# OKADIRI_1stGroup.net
KiCad netlist of a schematic drawn in EAGLE
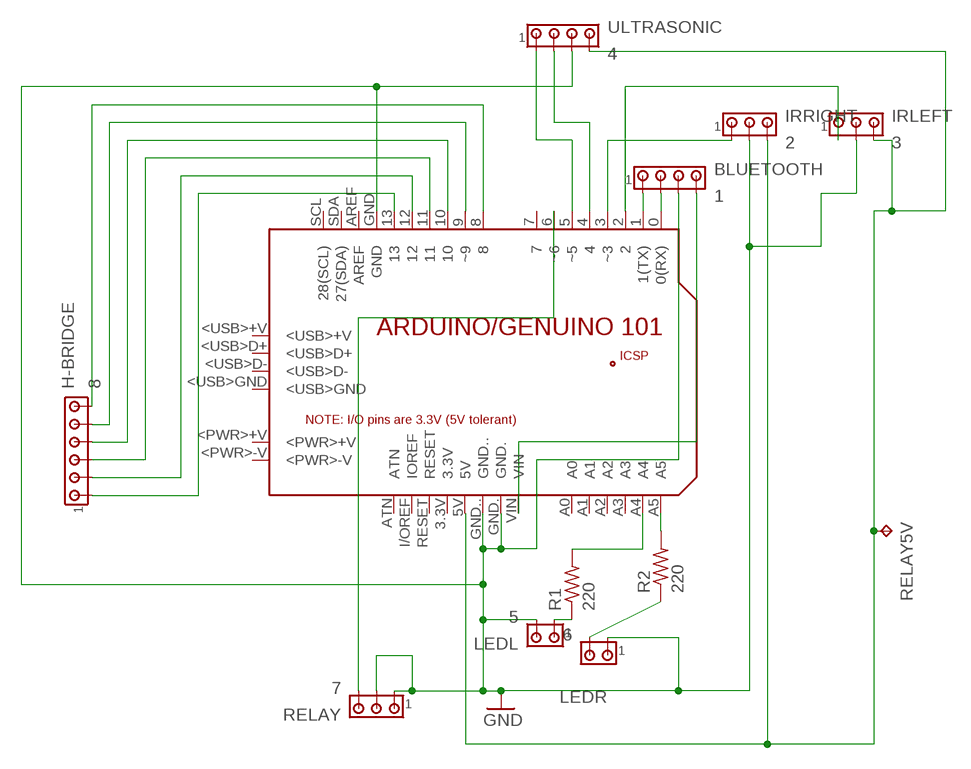
[diagram p0: schematic, sheet 1]

(export (version "E")
  (design (tool "Eeschema 10.0.6"))
  (components
    (comp (ref "BLUETOOTH")
      (value "1")
      (footprint "eagle-import:10X04MTA")
      (libsource (lib "eagle-import") (part "MTA04-100"))
    )
    (comp (ref "H-BRIDGE")
      (value "8")
      (footprint "eagle-import:10X06MTA")
      (libsource (lib "eagle-import") (part "MTA06-100"))
    )
    (comp (ref "IRLEFT")
      (value "3")
      (footprint "eagle-import:10X03MTA")
      (libsource (lib "eagle-import") (part "MTA03-100"))
    )
    (comp (ref "IRRIGHT")
      (value "2")
      (footprint "eagle-import:10X03MTA")
      (libsource (lib "eagle-import") (part "MTA03-100"))
    )
    (comp (ref "LEDL")
      (value "5")
      (footprint "eagle-import:10X02MTA")
      (libsource (lib "eagle-import") (part "MTA02-100"))
    )
    (comp (ref "LEDR")
      (value "6")
      (footprint "eagle-import:10X02MTA")
      (libsource (lib "eagle-import") (part "MTA02-100"))
    )
    (comp (ref "PCB1")
      (value "ARDUINO_101")
      (footprint "eagle-import:ARDUINO_101")
      (libsource (lib "eagle-import") (part "ARDUINO_101"))
    )
    (comp (ref "R1")
      (value "220")
      (footprint "eagle-import:0309_10")
      (libsource (lib "eagle-import") (part "R-US_0309/10"))
    )
    (comp (ref "R2")
      (value "220")
      (footprint "eagle-import:0309_10")
      (libsource (lib "eagle-import") (part "R-US_0309/10"))
    )
    (comp (ref "RELAY")
      (value "7")
      (footprint "eagle-import:10X03MTA")
      (libsource (lib "eagle-import") (part "MTA03-100"))
    )
    (comp (ref "RELAY5V")
      (value "TPPAD1-13Y")
      (footprint "eagle-import:P1-13Y")
      (libsource (lib "eagle-import") (part "TPPAD1-13Y"))
    )
    (comp (ref "ULTRASONIC")
      (value "4")
      (footprint "eagle-import:10X04MTA")
      (libsource (lib "eagle-import") (part "MTA04-100"))
    )
  )
  (nets
    (net (code "1") (name "GND") (class "Default")
      (node (ref "BLUETOOTH") (pin "3") (pinfunction "3_3") (pintype "passive"))
      (node (ref "IRLEFT") (pin "2") (pinfunction "2_2") (pintype "passive"))
      (node (ref "IRRIGHT") (pin "2") (pinfunction "2_2") (pintype "passive"))
      (node (ref "LEDL") (pin "2") (pinfunction "2_2") (pintype "passive"))
      (node (ref "LEDR") (pin "1") (pinfunction "1_1") (pintype "passive"))
      (node (ref "PCB1") (pin "GND") (pinfunction "GND_GND") (pintype "bidirectional"))
      (node (ref "PCB1") (pin "GND.") (pinfunction "GND._GND.") (pintype "bidirectional"))
      (node (ref "PCB1") (pin "GND..") (pinfunction "GND.._GND..") (pintype "bidirectional"))
      (node (ref "RELAY") (pin "1") (pinfunction "1_1") (pintype "passive"))
      (node (ref "RELAY") (pin "2") (pinfunction "2_2") (pintype "passive"))
      (node (ref "ULTRASONIC") (pin "3") (pinfunction "3_3") (pintype "passive"))
    )
    (net (code "2") (name "Net-(BLUETOOTH-Pad4)") (class "Default")
      (node (ref "BLUETOOTH") (pin "4") (pinfunction "4_4") (pintype "passive"))
      (node (ref "PCB1") (pin "VIN") (pinfunction "VIN_VIN") (pintype "bidirectional"))
    )
    (net (code "3") (name "Net-(H-BRIDGE-Pad1)") (class "Default")
      (node (ref "H-BRIDGE") (pin "1") (pinfunction "1_1") (pintype "passive"))
      (node (ref "PCB1") (pin "13") (pinfunction "13_13") (pintype "bidirectional"))
    )
    (net (code "4") (name "Net-(H-BRIDGE-Pad2)") (class "Default")
      (node (ref "H-BRIDGE") (pin "2") (pinfunction "2_2") (pintype "passive"))
      (node (ref "PCB1") (pin "12") (pinfunction "12_12") (pintype "bidirectional"))
    )
    (net (code "5") (name "Net-(H-BRIDGE-Pad3)") (class "Default")
      (node (ref "H-BRIDGE") (pin "3") (pinfunction "3_3") (pintype "passive"))
      (node (ref "PCB1") (pin "11") (pinfunction "11_11") (pintype "bidirectional"))
    )
    (net (code "6") (name "Net-(H-BRIDGE-Pad4)") (class "Default")
      (node (ref "H-BRIDGE") (pin "4") (pinfunction "4_4") (pintype "passive"))
      (node (ref "PCB1") (pin "10") (pinfunction "10_10") (pintype "bidirectional"))
    )
    (net (code "7") (name "Net-(H-BRIDGE-Pad6)") (class "Default")
      (node (ref "H-BRIDGE") (pin "6") (pinfunction "6_6") (pintype "passive"))
      (node (ref "PCB1") (pin "8") (pinfunction "8_8") (pintype "bidirectional"))
    )
    (net (code "8") (name "Net-(IRLEFT-Pad1)") (class "Default")
      (node (ref "IRLEFT") (pin "1") (pinfunction "1_1") (pintype "passive"))
      (node (ref "PCB1") (pin "2") (pinfunction "2_2") (pintype "bidirectional"))
    )
    (net (code "9") (name "Net-(IRLEFT-Pad3)") (class "Default")
      (node (ref "IRLEFT") (pin "3") (pinfunction "3_3") (pintype "passive"))
      (node (ref "IRRIGHT") (pin "3") (pinfunction "3_3") (pintype "passive"))
      (node (ref "PCB1") (pin "5V") (pinfunction "5V_5V") (pintype "bidirectional"))
      (node (ref "RELAY5V") (pin "TP") (pinfunction "TP_TP") (pintype "input"))
      (node (ref "ULTRASONIC") (pin "4") (pinfunction "4_4") (pintype "passive"))
    )
    (net (code "10") (name "Net-(LEDL-Pad1)") (class "Default")
      (node (ref "LEDL") (pin "1") (pinfunction "1_1") (pintype "passive"))
      (node (ref "R1") (pin "1") (pinfunction "1_1") (pintype "passive"))
    )
    (net (code "11") (name "Net-(LEDR-Pad2)") (class "Default")
      (node (ref "LEDR") (pin "2") (pinfunction "2_2") (pintype "passive"))
      (node (ref "R2") (pin "1") (pinfunction "1_1") (pintype "passive"))
    )
    (net (code "12") (name "Net-(PCB1-0(RX))") (class "Default")
      (node (ref "BLUETOOTH") (pin "2") (pinfunction "2_2") (pintype "passive"))
      (node (ref "PCB1") (pin "0") (pinfunction "0(RX)_0") (pintype "bidirectional"))
    )
    (net (code "13") (name "Net-(PCB1-1(TX))") (class "Default")
      (node (ref "BLUETOOTH") (pin "1") (pinfunction "1_1") (pintype "passive"))
      (node (ref "PCB1") (pin "1") (pinfunction "1(TX)_1") (pintype "bidirectional"))
    )
    (net (code "14") (name "Net-(PCB1-Pad4)") (class "Default")
      (node (ref "PCB1") (pin "4") (pinfunction "4_4") (pintype "bidirectional"))
      (node (ref "ULTRASONIC") (pin "2") (pinfunction "2_2") (pintype "passive"))
    )
    (net (code "15") (name "Net-(PCB1-PadA4)") (class "Default")
      (node (ref "PCB1") (pin "A4") (pinfunction "A4_A4") (pintype "bidirectional"))
      (node (ref "R1") (pin "2") (pinfunction "2_2") (pintype "passive"))
    )
    (net (code "16") (name "Net-(PCB1-PadA5)") (class "Default")
      (node (ref "PCB1") (pin "A5") (pinfunction "A5_A5") (pintype "bidirectional"))
      (node (ref "R2") (pin "2") (pinfunction "2_2") (pintype "passive"))
    )
    (net (code "17") (name "Net-(PCB1-~{3})") (class "Default")
      (node (ref "IRRIGHT") (pin "1") (pinfunction "1_1") (pintype "passive"))
      (node (ref "PCB1") (pin "3") (pinfunction "~{3}_3") (pintype "bidirectional"))
    )
    (net (code "18") (name "Net-(PCB1-~{5})") (class "Default")
      (node (ref "PCB1") (pin "5") (pinfunction "~{5}_5") (pintype "bidirectional"))
      (node (ref "ULTRASONIC") (pin "1") (pinfunction "1_1") (pintype "passive"))
    )
    (net (code "19") (name "Net-(PCB1-~{6})") (class "Default")
      (node (ref "PCB1") (pin "6") (pinfunction "~{6}_6") (pintype "bidirectional"))
      (node (ref "RELAY") (pin "3") (pinfunction "3_3") (pintype "passive"))
    )
    (net (code "20") (name "Net-(PCB1-~{9})") (class "Default")
      (node (ref "H-BRIDGE") (pin "5") (pinfunction "5_5") (pintype "passive"))
      (node (ref "PCB1") (pin "9") (pinfunction "~{9}_9") (pintype "bidirectional"))
    )
    (net (code "21") (name "unconnected-(PCB1-27(SDA)-PadSDA)") (class "Default")
      (node (ref "PCB1") (pin "SDA") (pinfunction "27(SDA)_SDA") (pintype "bidirectional"))
    )
    (net (code "22") (name "unconnected-(PCB1-28(SCL)-PadSCL)") (class "Default")
      (node (ref "PCB1") (pin "SCL") (pinfunction "28(SCL)_SCL") (pintype "bidirectional"))
    )
    (net (code "23") (name "unconnected-(PCB1-IOREF-PadI{slash}OREF)") (class "Default")
      (node (ref "PCB1") (pin "I/OREF") (pinfunction "IOREF_I/OREF") (pintype "bidirectional"))
    )
    (net (code "24") (name "unconnected-(PCB1-Pad+5V)") (class "Default")
      (node (ref "PCB1") (pin "+5V") (pinfunction "+5V_+5V") (pintype "bidirectional"))
    )
    (net (code "25") (name "unconnected-(PCB1-Pad3.3V)") (class "Default")
      (node (ref "PCB1") (pin "3.3V") (pinfunction "3.3V_3.3V") (pintype "bidirectional"))
    )
    (net (code "26") (name "unconnected-(PCB1-Pad7)") (class "Default")
      (node (ref "PCB1") (pin "7") (pinfunction "7_7") (pintype "bidirectional"))
    )
    (net (code "27") (name "unconnected-(PCB1-Pad<PWR>+V)") (class "Default")
      (node (ref "PCB1") (pin "<PWR>+V") (pinfunction "<PWR>+V_<PWR>+V") (pintype "bidirectional"))
    )
    (net (code "28") (name "unconnected-(PCB1-Pad<PWR>-V)") (class "Default")
      (node (ref "PCB1") (pin "<PWR>-V") (pinfunction "<PWR>-V_<PWR>-V") (pintype "bidirectional"))
    )
    (net (code "29") (name "unconnected-(PCB1-Pad<USB>+V)") (class "Default")
      (node (ref "PCB1") (pin "<USB>+V") (pinfunction "<USB>+V_<USB>+V") (pintype "bidirectional"))
    )
    (net (code "30") (name "unconnected-(PCB1-Pad<USB>D+)") (class "Default")
      (node (ref "PCB1") (pin "<USB>D+") (pinfunction "<USB>D+_<USB>D+") (pintype "bidirectional"))
    )
    (net (code "31") (name "unconnected-(PCB1-Pad<USB>D-)") (class "Default")
      (node (ref "PCB1") (pin "<USB>D-") (pinfunction "<USB>D-_<USB>D-") (pintype "bidirectional"))
    )
    (net (code "32") (name "unconnected-(PCB1-Pad<USB>GND)") (class "Default")
      (node (ref "PCB1") (pin "<USB>GND") (pinfunction "<USB>GND_<USB>GND") (pintype "bidirectional"))
    )
    (net (code "33") (name "unconnected-(PCB1-PadA0)") (class "Default")
      (node (ref "PCB1") (pin "A0") (pinfunction "A0_A0") (pintype "bidirectional"))
    )
    (net (code "34") (name "unconnected-(PCB1-PadA1)") (class "Default")
      (node (ref "PCB1") (pin "A1") (pinfunction "A1_A1") (pintype "bidirectional"))
    )
    (net (code "35") (name "unconnected-(PCB1-PadA2)") (class "Default")
      (node (ref "PCB1") (pin "A2") (pinfunction "A2_A2") (pintype "bidirectional"))
    )
    (net (code "36") (name "unconnected-(PCB1-PadA3)") (class "Default")
      (node (ref "PCB1") (pin "A3") (pinfunction "A3_A3") (pintype "bidirectional"))
    )
    (net (code "37") (name "unconnected-(PCB1-PadAREF)") (class "Default")
      (node (ref "PCB1") (pin "AREF") (pinfunction "AREF_AREF") (pintype "bidirectional"))
    )
    (net (code "38") (name "unconnected-(PCB1-PadATN)") (class "Default")
      (node (ref "PCB1") (pin "ATN") (pinfunction "ATN_ATN") (pintype "bidirectional"))
    )
    (net (code "39") (name "unconnected-(PCB1-PadGND_)") (class "Default")
      (node (ref "PCB1") (pin "GND_") (pinfunction "GND__GND_") (pintype "bidirectional"))
    )
    (net (code "40") (name "unconnected-(PCB1-PadMISO)") (class "Default")
      (node (ref "PCB1") (pin "MISO") (pinfunction "MISO_MISO") (pintype "bidirectional"))
    )
    (net (code "41") (name "unconnected-(PCB1-PadMOSI)") (class "Default")
      (node (ref "PCB1") (pin "MOSI") (pinfunction "MOSI_MOSI") (pintype "bidirectional"))
    )
    (net (code "42") (name "unconnected-(PCB1-PadRESET)") (class "Default")
      (node (ref "PCB1") (pin "RESET") (pinfunction "RESET_RESET") (pintype "bidirectional"))
    )
    (net (code "43") (name "unconnected-(PCB1-PadRESET.)") (class "Default")
      (node (ref "PCB1") (pin "RESET.") (pinfunction "RESET._RESET.") (pintype "bidirectional"))
    )
    (net (code "44") (name "unconnected-(PCB1-PadSCK)") (class "Default")
      (node (ref "PCB1") (pin "SCK") (pinfunction "SCK_SCK") (pintype "bidirectional"))
    )
  )
)
